# Power.net
KiCad netlist of a schematic drawn in Altium Designer
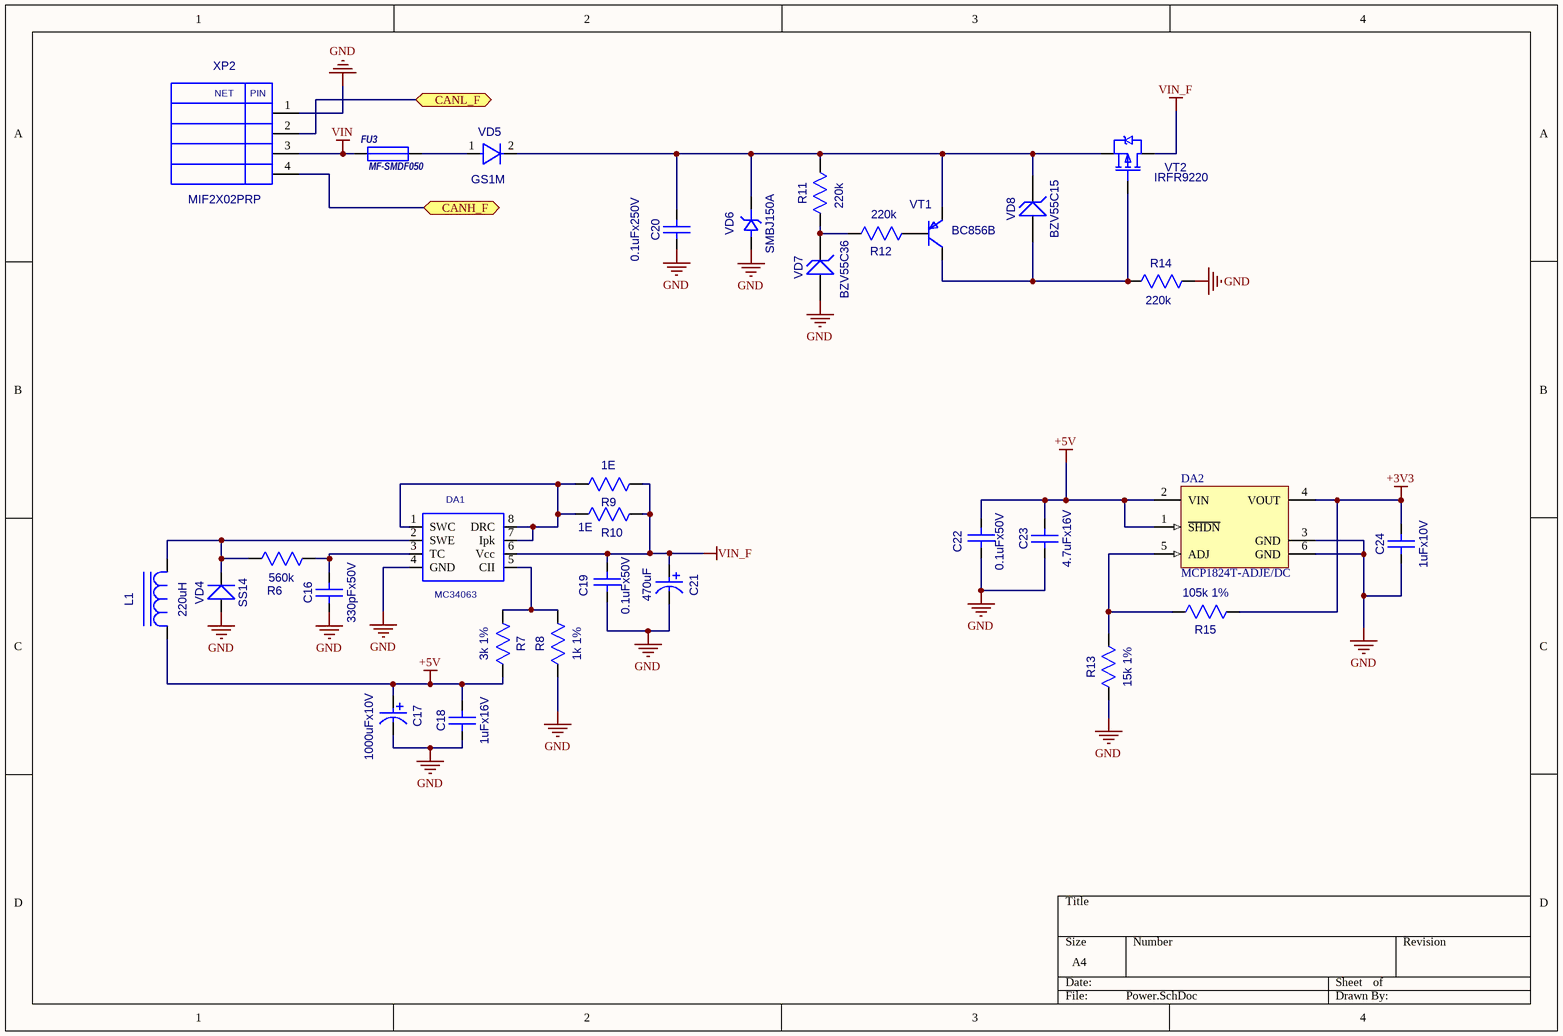
[diagram p0: Power.SchDoc]

(export (version "E")
  (design (tool "Eeschema 10.0.6"))
  (components
    (comp (ref "C16")
      (value "330pFx50V")
      (footprint "CC0603-3M")
      (description "CC0603")
      (libsource (lib "gprs_modem") (part "CC0603"))
    )
    (comp (ref "C17")
      (value "1000uFx10V")
      (footprint "CC8X3.5")
      (description "CAP0.35")
      (libsource (lib "gprs_modem") (part "CAP0.35"))
    )
    (comp (ref "C18")
      (value "1uFx16V")
      (footprint "CC0603-3M")
      (description "CC0603")
      (libsource (lib "gprs_modem") (part "CC0603"))
    )
    (comp (ref "C19")
      (value "0.1uFx50V")
      (footprint "CC0603-3M")
      (description "CC0603")
      (libsource (lib "gprs_modem") (part "CC0603"))
    )
    (comp (ref "C20")
      (value "0.1uFx250V")
      (footprint "CC1206-MIDI")
      (description "CC1206")
      (libsource (lib "gprs_modem") (part "CC1206"))
    )
    (comp (ref "C21")
      (value "470uF")
      (footprint "CC16X10_CAP0.5(1)(Primary)")
      (description "CAP0.5(1)")
      (libsource (lib "gprs_modem") (part "CAP0.5(1)"))
    )
    (comp (ref "C22")
      (value "0.1uFx50V")
      (footprint "CC0603-3M")
      (description "CC0603")
      (libsource (lib "gprs_modem") (part "CC0603"))
    )
    (comp (ref "C23")
      (value "4.7uFx16V")
      (footprint "CC0805-MIDI-2M1")
      (description "CC0805")
      (libsource (lib "gprs_modem") (part "CC0805"))
    )
    (comp (ref "C24")
      (value "1uFx10V")
      (footprint "CC0603-3M")
      (description "CC0603")
      (libsource (lib "gprs_modem") (part "CC0603"))
    )
    (comp (ref "DA1") (value "MC34063") (footprint "SO-8") (libsource (lib "Schetchik") (part "MC34063")))
    (comp (ref "DA2")
      (value "MCP1824T-ADJE/DC")
      (footprint "SOT223-6")
      (fields (field (name "PUBLISHER") "Altium Limited"))
      (libsource (lib "gprs_modem") (part "MCP1824T-ADJE/DC"))
    )
    (comp (ref "FU3")
      (value "MF-SMDF050")
      (footprint "MF-SMDF")
      (description "MF-SMDF")
      (libsource (lib "gprs_modem") (part "MF-SMDF"))
    )
    (comp (ref "L1")
      (value "220uH")
      (footprint "SDR0805")
      (description "SDR0805")
      (libsource (lib "gprs_modem") (part "SDR0805"))
    )
    (comp (ref "R6")
      (value "560k")
      (footprint "RC0603-3M")
      (description "RC0603")
      (libsource (lib "gprs_modem") (part "RC0603"))
    )
    (comp (ref "R7")
      (value "3k 1%")
      (footprint "RC0603-3M")
      (description "RC0603")
      (libsource (lib "gprs_modem") (part "RC0603"))
    )
    (comp (ref "R8")
      (value "1k 1%")
      (footprint "RC0603-3M")
      (description "RC0603")
      (libsource (lib "gprs_modem") (part "RC0603"))
    )
    (comp (ref "R9")
      (value "1E")
      (footprint "RC0805_IPC_NOM")
      (description "RC0805")
      (libsource (lib "gprs_modem") (part "RC0805"))
    )
    (comp (ref "R10")
      (value "1E")
      (footprint "RC0805_IPC_NOM")
      (description "RC0805")
      (libsource (lib "gprs_modem") (part "RC0805"))
    )
    (comp (ref "R11")
      (value "220k")
      (footprint "RC1206-2M")
      (description "RC1206")
      (libsource (lib "gprs_modem") (part "RC1206"))
    )
    (comp (ref "R12")
      (value "220k")
      (footprint "RC1206-2M")
      (description "RC1206")
      (libsource (lib "gprs_modem") (part "RC1206"))
    )
    (comp (ref "R13")
      (value "15k 1%")
      (footprint "RC0603-3M")
      (description "RC0603")
      (libsource (lib "gprs_modem") (part "RC0603"))
    )
    (comp (ref "R14")
      (value "220k")
      (footprint "RC1206-2M")
      (description "RC1206")
      (libsource (lib "gprs_modem") (part "RC1206"))
    )
    (comp (ref "R15")
      (value "105k 1%")
      (footprint "RC0603-3M")
      (description "RC0603")
      (libsource (lib "gprs_modem") (part "RC0603"))
    )
    (comp (ref "VD4")
      (value "SS14")
      (footprint "SMA")
      (description "Schottky Rectifier")
      (libsource (lib "gprs_modem") (part "SS14"))
    )
    (comp (ref "VD5") (value "GS1M") (footprint "SMA") (libsource (lib "Schetchik") (part "GS1M")))
    (comp (ref "VD6")
      (value "SMBJ150A")
      (footprint "SMB")
      (description "SMBJ")
      (libsource (lib "gprs_modem") (part "SMBJ"))
    )
    (comp (ref "VD7")
      (value "BZV55C36")
      (footprint "SOD-80")
      (description "Zener Voltage Regulator Diode")
      (libsource (lib "gprs_modem") (part "BZV55C12"))
    )
    (comp (ref "VD8")
      (value "BZV55C15")
      (footprint "SOD-80")
      (description "Zener Voltage Regulator Diode")
      (libsource (lib "gprs_modem") (part "BZV55C12"))
    )
    (comp (ref "VT1")
      (value "BC856B")
      (footprint "SOT-23(123)")
      (libsource (lib "Schetchik") (part "BC856B"))
    )
    (comp (ref "VT2")
      (value "IRFR9220")
      (footprint "D-PAK(TO-252AA)")
      (description "HEXFET Power MOSFET")
      (libsource (lib "gprs_modem") (part "IRFR9220"))
    )
    (comp (ref "XP2")
      (value "MIF2X02PRP")
      (footprint "MIF2X02PRP")
      (libsource (lib "Schetchik") (part "MIF2X02PRP"))
    )
  )
  (nets
    (net (code "1") (name "+3V3") (class "Default")
      (node (ref "C24") (pin "2") (pinfunction "B_2") (pintype "passive"))
      (node (ref "DA2") (pin "4") (pinfunction "VOUT_4") (pintype "power_in"))
      (node (ref "R15") (pin "1") (pinfunction "A_1") (pintype "passive"))
    )
    (net (code "2") (name "+5V") (class "Default")
      (node (ref "C17") (pin "1") (pintype "passive"))
      (node (ref "C18") (pin "2") (pinfunction "B_2") (pintype "passive"))
      (node (ref "C22") (pin "1") (pinfunction "A_1") (pintype "passive"))
      (node (ref "C23") (pin "2") (pinfunction "B_2") (pintype "passive"))
      (node (ref "DA2") (pin "1") (pinfunction "~{SHDN}_1") (pintype "input"))
      (node (ref "DA2") (pin "2") (pinfunction "VIN_2") (pintype "power_in"))
      (node (ref "L1") (pin "1") (pinfunction "C_1") (pintype "passive"))
      (node (ref "R7") (pin "2") (pinfunction "B_2") (pintype "passive"))
    )
    (net (code "3") (name "/CANH_F") (class "Default")
      (node (ref "XP2") (pin "4") (pinfunction "4_4") (pintype "passive"))
    )
    (net (code "4") (name "/CANL_F") (class "Default")
      (node (ref "XP2") (pin "2") (pinfunction "2_2") (pintype "passive"))
    )
    (net (code "5") (name "GND") (class "Default")
      (node (ref "C16") (pin "1") (pinfunction "A_1") (pintype "passive"))
      (node (ref "C17") (pin "2") (pintype "passive"))
      (node (ref "C18") (pin "1") (pinfunction "A_1") (pintype "passive"))
      (node (ref "C19") (pin "2") (pinfunction "B_2") (pintype "passive"))
      (node (ref "C20") (pin "1") (pinfunction "A_1") (pintype "passive"))
      (node (ref "C21") (pin "1") (pintype "passive"))
      (node (ref "C22") (pin "2") (pinfunction "B_2") (pintype "passive"))
      (node (ref "C23") (pin "1") (pinfunction "A_1") (pintype "passive"))
      (node (ref "C24") (pin "1") (pinfunction "A_1") (pintype "passive"))
      (node (ref "DA1") (pin "4") (pinfunction "GND_4") (pintype "passive"))
      (node (ref "DA2") (pin "3") (pinfunction "GND_3") (pintype "power_in"))
      (node (ref "DA2") (pin "6") (pinfunction "GND_6") (pintype "power_in"))
      (node (ref "R13") (pin "1") (pinfunction "A_1") (pintype "passive"))
      (node (ref "R14") (pin "2") (pinfunction "B_2") (pintype "passive"))
      (node (ref "R8") (pin "1") (pinfunction "A_1") (pintype "passive"))
      (node (ref "VD4") (pin "1") (pinfunction "A_1") (pintype "passive"))
      (node (ref "VD6") (pin "1") (pinfunction "A_1") (pintype "passive"))
      (node (ref "VD7") (pin "1") (pinfunction "A_1") (pintype "passive"))
      (node (ref "XP2") (pin "1") (pinfunction "1_1") (pintype "passive"))
    )
    (net (code "6") (name "Net-(C16-B)") (class "Default")
      (node (ref "C16") (pin "2") (pinfunction "B_2") (pintype "passive"))
      (node (ref "DA1") (pin "3") (pinfunction "TC_3") (pintype "passive"))
      (node (ref "R6") (pin "2") (pinfunction "B_2") (pintype "passive"))
    )
    (net (code "7") (name "Net-(C20-B)") (class "Default")
      (node (ref "C20") (pin "2") (pinfunction "B_2") (pintype "passive"))
      (node (ref "R11") (pin "2") (pinfunction "B_2") (pintype "passive"))
      (node (ref "VD5") (pin "2") (pinfunction "K_2") (pintype "passive"))
      (node (ref "VD6") (pin "2") (pinfunction "K_2") (pintype "passive"))
      (node (ref "VD8") (pin "2") (pintype "passive"))
      (node (ref "VT1") (pin "2") (pinfunction "E_2") (pintype "passive"))
      (node (ref "VT2") (pin "2") (pinfunction "S_2") (pintype "passive"))
    )
    (net (code "8") (name "Net-(DA1-CII)") (class "Default")
      (node (ref "DA1") (pin "5") (pinfunction "CII_5") (pintype "passive"))
      (node (ref "R7") (pin "1") (pinfunction "A_1") (pintype "passive"))
      (node (ref "R8") (pin "2") (pinfunction "B_2") (pintype "passive"))
    )
    (net (code "9") (name "Net-(DA1-DRC)") (class "Default")
      (node (ref "DA1") (pin "1") (pinfunction "SWC_1") (pintype "passive"))
      (node (ref "DA1") (pin "7") (pinfunction "Ipk_7") (pintype "passive"))
      (node (ref "DA1") (pin "8") (pinfunction "DRC_8") (pintype "passive"))
      (node (ref "R10") (pin "2") (pinfunction "B_2") (pintype "passive"))
      (node (ref "R9") (pin "2") (pinfunction "B_2") (pintype "passive"))
    )
    (net (code "10") (name "Net-(DA1-SWE)") (class "Default")
      (node (ref "DA1") (pin "2") (pinfunction "SWE_2") (pintype "passive"))
      (node (ref "L1") (pin "2") (pinfunction "A_2") (pintype "passive"))
      (node (ref "R6") (pin "1") (pinfunction "A_1") (pintype "passive"))
      (node (ref "VD4") (pin "2") (pinfunction "K_2") (pintype "passive"))
    )
    (net (code "11") (name "Net-(DA2-ADJ)") (class "Default")
      (node (ref "DA2") (pin "5") (pinfunction "ADJ_5") (pintype "input"))
      (node (ref "R13") (pin "2") (pinfunction "B_2") (pintype "passive"))
      (node (ref "R15") (pin "2") (pinfunction "B_2") (pintype "passive"))
    )
    (net (code "12") (name "Net-(R11-A)") (class "Default")
      (node (ref "R11") (pin "1") (pinfunction "A_1") (pintype "passive"))
      (node (ref "R12") (pin "2") (pinfunction "B_2") (pintype "passive"))
      (node (ref "VD7") (pin "2") (pintype "passive"))
    )
    (net (code "13") (name "Net-(R12-A)") (class "Default")
      (node (ref "R12") (pin "1") (pinfunction "A_1") (pintype "passive"))
      (node (ref "VT1") (pin "1") (pinfunction "B_1") (pintype "passive"))
    )
    (net (code "14") (name "Net-(R14-A)") (class "Default")
      (node (ref "R14") (pin "1") (pinfunction "A_1") (pintype "passive"))
      (node (ref "VD8") (pin "1") (pinfunction "A_1") (pintype "passive"))
      (node (ref "VT1") (pin "3") (pinfunction "C_3") (pintype "passive"))
      (node (ref "VT2") (pin "1") (pinfunction "G_1") (pintype "passive"))
    )
    (net (code "15") (name "Net-(VD5-A)") (class "Default")
      (node (ref "FU3") (pin "2") (pintype "passive"))
      (node (ref "VD5") (pin "1") (pinfunction "A_1") (pintype "passive"))
    )
    (net (code "16") (name "VIN") (class "Default")
      (node (ref "FU3") (pin "1") (pintype "passive"))
      (node (ref "XP2") (pin "3") (pinfunction "3_3") (pintype "passive"))
    )
    (net (code "17") (name "VIN_F") (class "Default")
      (node (ref "C19") (pin "1") (pinfunction "A_1") (pintype "passive"))
      (node (ref "C21") (pin "2") (pintype "passive"))
      (node (ref "DA1") (pin "6") (pinfunction "Vcc_6") (pintype "passive"))
      (node (ref "R10") (pin "1") (pinfunction "A_1") (pintype "passive"))
      (node (ref "R9") (pin "1") (pinfunction "A_1") (pintype "passive"))
      (node (ref "VT2") (pin "3") (pinfunction "D_3") (pintype "passive"))
    )
  )
)
